# Qwiic_Keypad.net
KiCad netlist of a schematic drawn in EAGLE
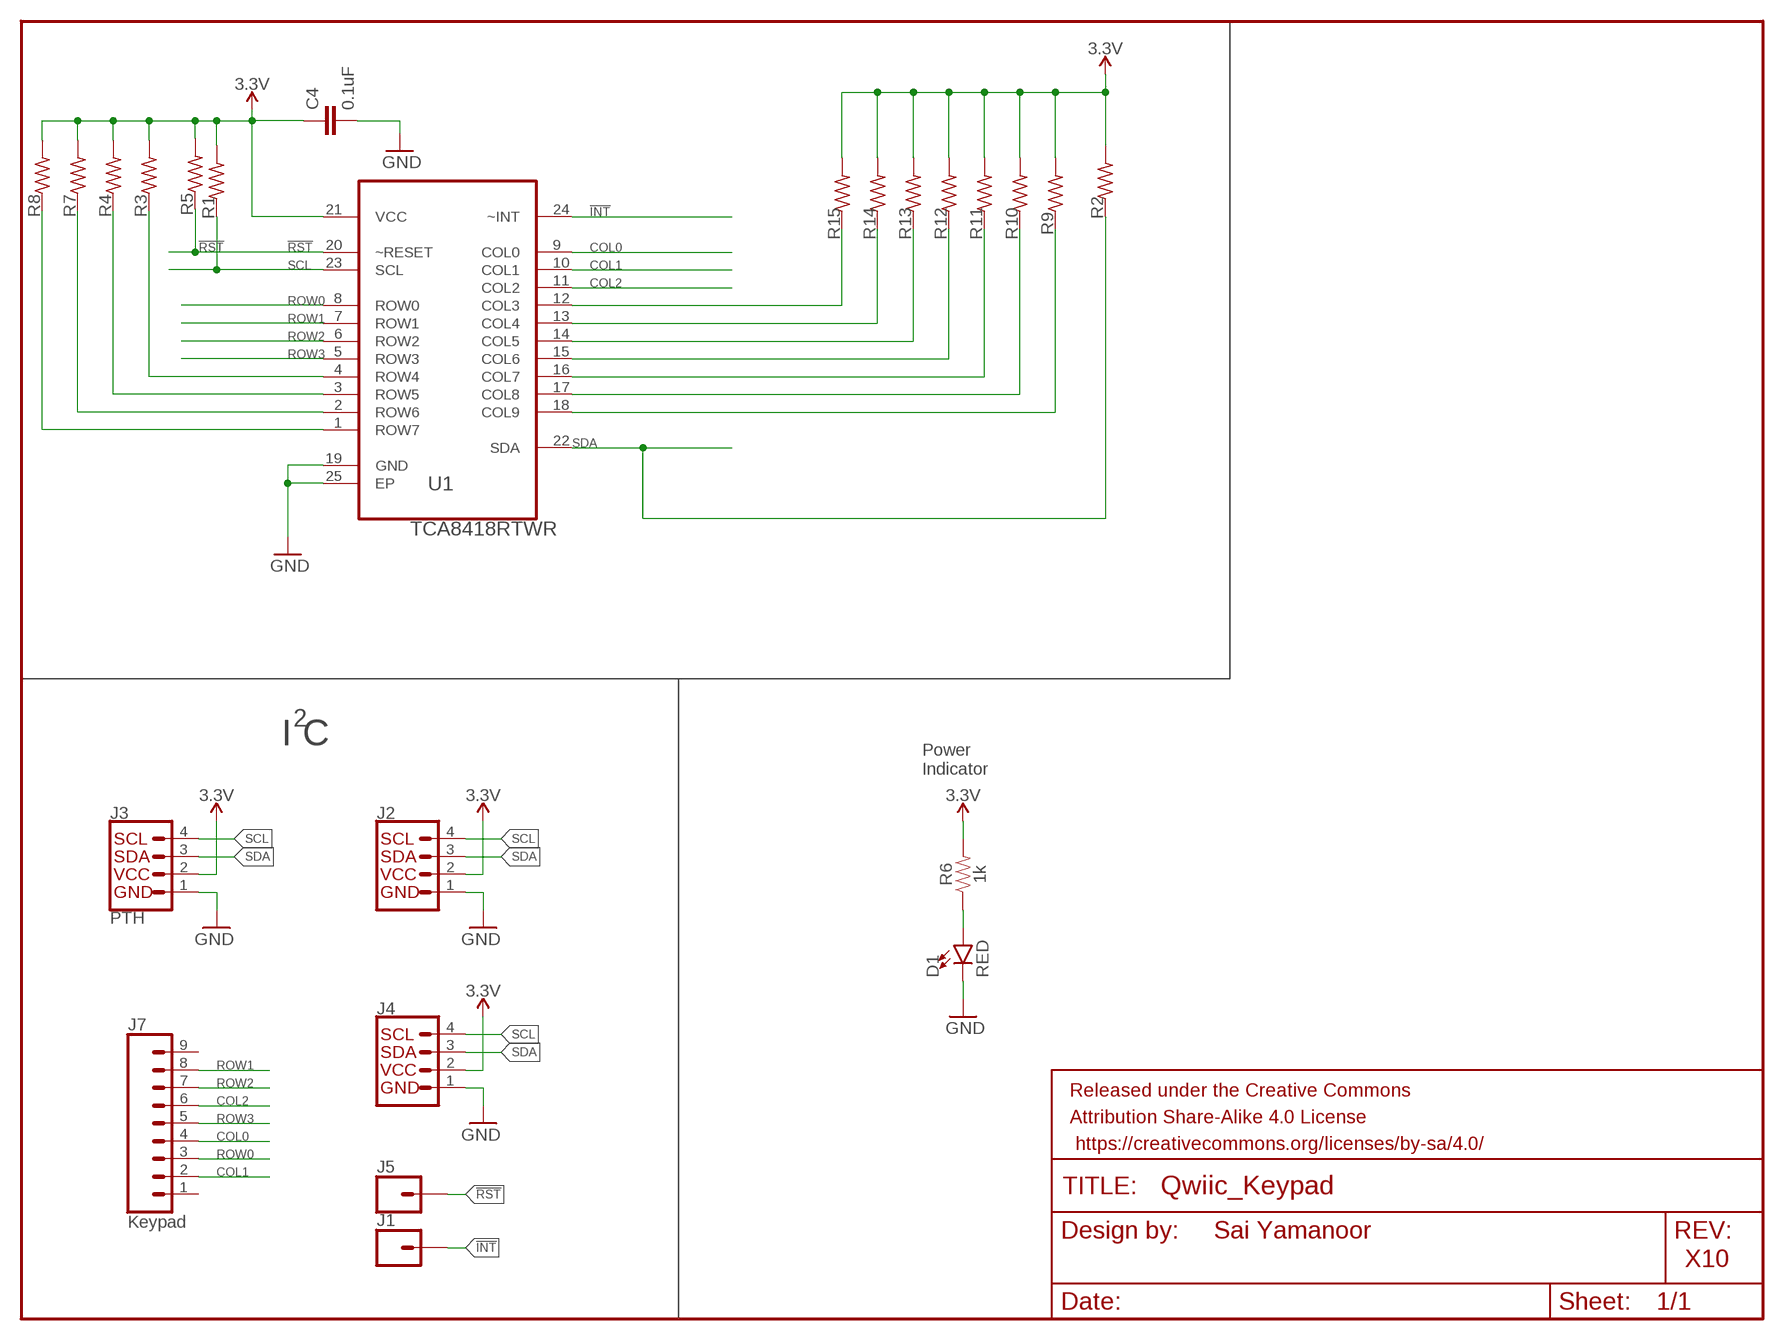
[diagram p0: schematic, sheet 1]

(export (version "E")
  (design (tool "Eeschema 10.0.6"))
  (components
    (comp (ref "C4")
      (value "0.1uF")
      (footprint "eagle-import:0603")
      (libsource (lib "eagle-import") (part "0.1UF-0603-25V-(+80/-20%)"))
    )
    (comp (ref "D1")
      (value "RED")
      (footprint "eagle-import:LED-0603")
      (libsource (lib "eagle-import") (part "LED-RED0603"))
    )
    (comp (ref "FRAME1")
      (value "FRAME-LETTER")
      (footprint "eagle-import:CREATIVE_COMMONS")
      (libsource (lib "eagle-import") (part "FRAME-LETTER"))
    )
    (comp (ref "J1")
      (value "CONN_01PTH_NO_SILK_YES_STOP")
      (footprint "eagle-import:1X01_NO_SILK")
      (libsource (lib "eagle-import") (part "CONN_01PTH_NO_SILK_YES_STOP"))
    )
    (comp (ref "J2")
      (value "QWIIC_CONNECTORJS-1MM")
      (footprint "eagle-import:1X04_1MM_RA")
      (libsource (lib "eagle-import") (part "QWIIC_CONNECTORJS-1MM"))
    )
    (comp (ref "J3")
      (value "PTH")
      (footprint "eagle-import:1X04_NO_SILK")
      (libsource (lib "eagle-import") (part "I2C_STANDARD_NO_SILK"))
    )
    (comp (ref "J4")
      (value "QWIIC_CONNECTORJS-1MM")
      (footprint "eagle-import:1X04_1MM_RA")
      (libsource (lib "eagle-import") (part "QWIIC_CONNECTORJS-1MM"))
    )
    (comp (ref "J5")
      (value "CONN_01PTH_NO_SILK_YES_STOP")
      (footprint "eagle-import:1X01_NO_SILK")
      (libsource (lib "eagle-import") (part "CONN_01PTH_NO_SILK_YES_STOP"))
    )
    (comp (ref "J7")
      (value "Keypad")
      (footprint "eagle-import:1X09_NO_SILK")
      (libsource (lib "eagle-import") (part "CONN_09NO_SILK"))
    )
    (comp (ref "R1")
      (value "4.7k")
      (footprint "eagle-import:R0402")
      (libsource (lib "eagle-import") (part "R-US_R0402"))
    )
    (comp (ref "R2")
      (value "4.7k")
      (footprint "eagle-import:R0402")
      (libsource (lib "eagle-import") (part "R-US_R0402"))
    )
    (comp (ref "R3")
      (value "10k")
      (footprint "eagle-import:R0402")
      (libsource (lib "eagle-import") (part "R-US_R0402"))
    )
    (comp (ref "R4")
      (value "10k")
      (footprint "eagle-import:R0402")
      (libsource (lib "eagle-import") (part "R-US_R0402"))
    )
    (comp (ref "R5")
      (value "10k")
      (footprint "eagle-import:R0402")
      (libsource (lib "eagle-import") (part "R-US_R0402"))
    )
    (comp (ref "R6")
      (value "1k")
      (footprint "eagle-import:0603")
      (libsource (lib "eagle-import") (part "1KOHM-0603-1/10W-1%"))
    )
    (comp (ref "R7")
      (value "10k")
      (footprint "eagle-import:R0402")
      (libsource (lib "eagle-import") (part "R-US_R0402"))
    )
    (comp (ref "R8")
      (value "10k")
      (footprint "eagle-import:R0402")
      (libsource (lib "eagle-import") (part "R-US_R0402"))
    )
    (comp (ref "R9")
      (value "10k")
      (footprint "eagle-import:R0402")
      (libsource (lib "eagle-import") (part "R-US_R0402"))
    )
    (comp (ref "R10")
      (value "10k")
      (footprint "eagle-import:R0402")
      (libsource (lib "eagle-import") (part "R-US_R0402"))
    )
    (comp (ref "R11")
      (value "10k")
      (footprint "eagle-import:R0402")
      (libsource (lib "eagle-import") (part "R-US_R0402"))
    )
    (comp (ref "R12")
      (value "10k")
      (footprint "eagle-import:R0402")
      (libsource (lib "eagle-import") (part "R-US_R0402"))
    )
    (comp (ref "R13")
      (value "10k")
      (footprint "eagle-import:R0402")
      (libsource (lib "eagle-import") (part "R-US_R0402"))
    )
    (comp (ref "R14")
      (value "10k")
      (footprint "eagle-import:R0402")
      (libsource (lib "eagle-import") (part "R-US_R0402"))
    )
    (comp (ref "R15")
      (value "10k")
      (footprint "eagle-import:R0402")
      (libsource (lib "eagle-import") (part "R-US_R0402"))
    )
    (comp (ref "U1")
      (value "TCA8418RTWR")
      (footprint "eagle-import:QFN50P400X400X80-25N")
      (fields (field (name "MF") "Texas Instruments"))
      (libsource (lib "eagle-import") (part "TCA8418RTWR"))
    )
  )
  (nets
    (net (code "1") (name "/COL0") (class "Default")
      (node (ref "J7") (pin "4") (pinfunction "4_4") (pintype "passive"))
      (node (ref "U1") (pin "9") (pinfunction "COL0_9") (pintype "bidirectional"))
    )
    (net (code "2") (name "/COL1") (class "Default")
      (node (ref "J7") (pin "2") (pinfunction "2_2") (pintype "passive"))
      (node (ref "U1") (pin "10") (pinfunction "COL1_10") (pintype "bidirectional"))
    )
    (net (code "3") (name "/COL2") (class "Default")
      (node (ref "J7") (pin "6") (pinfunction "6_6") (pintype "passive"))
      (node (ref "U1") (pin "11") (pinfunction "COL2_11") (pintype "bidirectional"))
    )
    (net (code "4") (name "/ROW0") (class "Default")
      (node (ref "J7") (pin "3") (pinfunction "3_3") (pintype "passive"))
      (node (ref "U1") (pin "8") (pinfunction "ROW0_8") (pintype "bidirectional"))
    )
    (net (code "5") (name "/ROW1") (class "Default")
      (node (ref "J7") (pin "8") (pinfunction "8_8") (pintype "passive"))
      (node (ref "U1") (pin "7") (pinfunction "ROW1_7") (pintype "bidirectional"))
    )
    (net (code "6") (name "/ROW2") (class "Default")
      (node (ref "J7") (pin "7") (pinfunction "7_7") (pintype "passive"))
      (node (ref "U1") (pin "6") (pinfunction "ROW2_6") (pintype "bidirectional"))
    )
    (net (code "7") (name "/ROW3") (class "Default")
      (node (ref "J7") (pin "5") (pinfunction "5_5") (pintype "passive"))
      (node (ref "U1") (pin "5") (pinfunction "ROW3_5") (pintype "bidirectional"))
    )
    (net (code "8") (name "/~{INT}") (class "Default")
      (node (ref "J1") (pin "1") (pinfunction "1_1") (pintype "passive"))
      (node (ref "U1") (pin "24") (pinfunction "~{INT}_24") (pintype "output"))
    )
    (net (code "9") (name "/~{RST}") (class "Default")
      (node (ref "J5") (pin "1") (pinfunction "1_1") (pintype "passive"))
      (node (ref "R5") (pin "1") (pinfunction "1_1") (pintype "passive"))
      (node (ref "U1") (pin "20") (pinfunction "~{RESET}_20") (pintype "input"))
    )
    (net (code "10") (name "3.3V") (class "Default")
      (node (ref "C4") (pin "1") (pinfunction "1_1") (pintype "passive"))
      (node (ref "J2") (pin "2") (pinfunction "2_2") (pintype "power_in"))
      (node (ref "J3") (pin "2") (pinfunction "VCC_2") (pintype "power_in"))
      (node (ref "J4") (pin "2") (pinfunction "2_2") (pintype "power_in"))
      (node (ref "R1") (pin "2") (pinfunction "2_2") (pintype "passive"))
      (node (ref "R10") (pin "2") (pinfunction "2_2") (pintype "passive"))
      (node (ref "R11") (pin "2") (pinfunction "2_2") (pintype "passive"))
      (node (ref "R12") (pin "2") (pinfunction "2_2") (pintype "passive"))
      (node (ref "R13") (pin "2") (pinfunction "2_2") (pintype "passive"))
      (node (ref "R14") (pin "2") (pinfunction "2_2") (pintype "passive"))
      (node (ref "R15") (pin "2") (pinfunction "2_2") (pintype "passive"))
      (node (ref "R2") (pin "2") (pinfunction "2_2") (pintype "passive"))
      (node (ref "R3") (pin "2") (pinfunction "2_2") (pintype "passive"))
      (node (ref "R4") (pin "2") (pinfunction "2_2") (pintype "passive"))
      (node (ref "R5") (pin "2") (pinfunction "2_2") (pintype "passive"))
      (node (ref "R6") (pin "2") (pinfunction "2_2") (pintype "passive"))
      (node (ref "R7") (pin "2") (pinfunction "2_2") (pintype "passive"))
      (node (ref "R8") (pin "2") (pinfunction "2_2") (pintype "passive"))
      (node (ref "R9") (pin "2") (pinfunction "2_2") (pintype "passive"))
      (node (ref "U1") (pin "21") (pinfunction "VCC_21") (pintype "power_in"))
    )
    (net (code "11") (name "GND") (class "Default")
      (node (ref "C4") (pin "2") (pinfunction "2_2") (pintype "passive"))
      (node (ref "D1") (pin "C") (pinfunction "C_C") (pintype "passive"))
      (node (ref "J2") (pin "1") (pinfunction "1_1") (pintype "power_in"))
      (node (ref "J3") (pin "1") (pinfunction "GND_1") (pintype "power_in"))
      (node (ref "J4") (pin "1") (pinfunction "1_1") (pintype "power_in"))
      (node (ref "U1") (pin "19") (pinfunction "GND_19") (pintype "passive"))
      (node (ref "U1") (pin "25") (pinfunction "EP_25") (pintype "passive"))
    )
    (net (code "12") (name "Net-(D1-PadA)") (class "Default")
      (node (ref "D1") (pin "A") (pinfunction "A_A") (pintype "passive"))
      (node (ref "R6") (pin "1") (pinfunction "1_1") (pintype "passive"))
    )
    (net (code "13") (name "Net-(U1-COL3)") (class "Default")
      (node (ref "R15") (pin "1") (pinfunction "1_1") (pintype "passive"))
      (node (ref "U1") (pin "12") (pinfunction "COL3_12") (pintype "bidirectional"))
    )
    (net (code "14") (name "Net-(U1-COL4)") (class "Default")
      (node (ref "R14") (pin "1") (pinfunction "1_1") (pintype "passive"))
      (node (ref "U1") (pin "13") (pinfunction "COL4_13") (pintype "bidirectional"))
    )
    (net (code "15") (name "Net-(U1-COL5)") (class "Default")
      (node (ref "R13") (pin "1") (pinfunction "1_1") (pintype "passive"))
      (node (ref "U1") (pin "14") (pinfunction "COL5_14") (pintype "bidirectional"))
    )
    (net (code "16") (name "Net-(U1-COL6)") (class "Default")
      (node (ref "R12") (pin "1") (pinfunction "1_1") (pintype "passive"))
      (node (ref "U1") (pin "15") (pinfunction "COL6_15") (pintype "bidirectional"))
    )
    (net (code "17") (name "Net-(U1-COL7)") (class "Default")
      (node (ref "R11") (pin "1") (pinfunction "1_1") (pintype "passive"))
      (node (ref "U1") (pin "16") (pinfunction "COL7_16") (pintype "bidirectional"))
    )
    (net (code "18") (name "Net-(U1-COL8)") (class "Default")
      (node (ref "R10") (pin "1") (pinfunction "1_1") (pintype "passive"))
      (node (ref "U1") (pin "17") (pinfunction "COL8_17") (pintype "bidirectional"))
    )
    (net (code "19") (name "Net-(U1-COL9)") (class "Default")
      (node (ref "R9") (pin "1") (pinfunction "1_1") (pintype "passive"))
      (node (ref "U1") (pin "18") (pinfunction "COL9_18") (pintype "bidirectional"))
    )
    (net (code "20") (name "Net-(U1-ROW4)") (class "Default")
      (node (ref "R3") (pin "1") (pinfunction "1_1") (pintype "passive"))
      (node (ref "U1") (pin "4") (pinfunction "ROW4_4") (pintype "bidirectional"))
    )
    (net (code "21") (name "Net-(U1-ROW5)") (class "Default")
      (node (ref "R4") (pin "1") (pinfunction "1_1") (pintype "passive"))
      (node (ref "U1") (pin "3") (pinfunction "ROW5_3") (pintype "bidirectional"))
    )
    (net (code "22") (name "Net-(U1-ROW6)") (class "Default")
      (node (ref "R7") (pin "1") (pinfunction "1_1") (pintype "passive"))
      (node (ref "U1") (pin "2") (pinfunction "ROW6_2") (pintype "bidirectional"))
    )
    (net (code "23") (name "Net-(U1-ROW7)") (class "Default")
      (node (ref "R8") (pin "1") (pinfunction "1_1") (pintype "passive"))
      (node (ref "U1") (pin "1") (pinfunction "ROW7_1") (pintype "bidirectional"))
    )
    (net (code "24") (name "SCL") (class "Default")
      (node (ref "J2") (pin "4") (pinfunction "4_4") (pintype "passive"))
      (node (ref "J3") (pin "4") (pinfunction "SCL_4") (pintype "passive"))
      (node (ref "J4") (pin "4") (pinfunction "4_4") (pintype "passive"))
      (node (ref "R1") (pin "1") (pinfunction "1_1") (pintype "passive"))
      (node (ref "U1") (pin "23") (pinfunction "SCL_23") (pintype "input"))
    )
    (net (code "25") (name "SDA") (class "Default")
      (node (ref "J2") (pin "3") (pinfunction "3_3") (pintype "passive"))
      (node (ref "J3") (pin "3") (pinfunction "SDA_3") (pintype "passive"))
      (node (ref "J4") (pin "3") (pinfunction "3_3") (pintype "passive"))
      (node (ref "R2") (pin "1") (pinfunction "1_1") (pintype "passive"))
      (node (ref "U1") (pin "22") (pinfunction "SDA_22") (pintype "bidirectional"))
    )
    (net (code "26") (name "unconnected-(J7-Pad1)") (class "Default")
      (node (ref "J7") (pin "1") (pinfunction "1_1") (pintype "passive"))
    )
    (net (code "27") (name "unconnected-(J7-Pad9)") (class "Default")
      (node (ref "J7") (pin "9") (pinfunction "9_9") (pintype "passive"))
    )
  )
)
